# PCB-REMCON.net
KiCad netlist of a schematic drawn in EAGLE
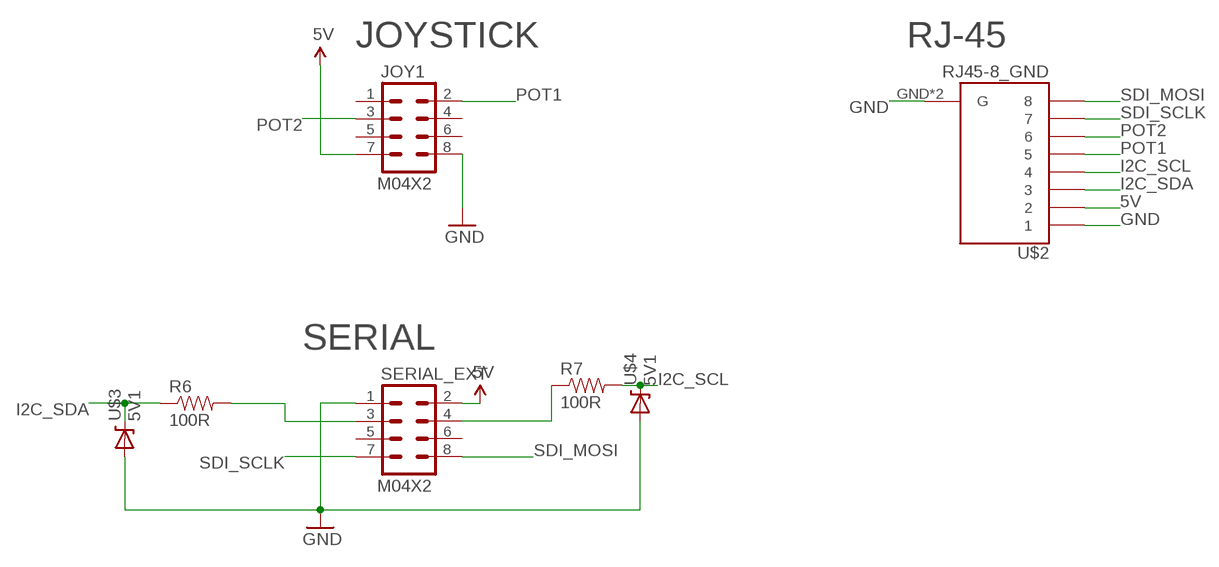
[diagram p0: schematic, sheet 1]

(export (version "E")
  (design (tool "Eeschema 10.0.6"))
  (components
    (comp (ref "JOY1")
      (value "M04X2")
      (footprint "eagle-import:2X4")
      (libsource (lib "eagle-import") (part "M04X2"))
    )
    (comp (ref "R6")
      (value "100R")
      (footprint "eagle-import:0603-RES")
      (libsource (lib "eagle-import") (part "RESISTOR0603-RES"))
    )
    (comp (ref "R7")
      (value "100R")
      (footprint "eagle-import:0603-RES")
      (libsource (lib "eagle-import") (part "RESISTOR0603-RES"))
    )
    (comp (ref "SERIAL_EXT")
      (value "M04X2")
      (footprint "eagle-import:2X4")
      (libsource (lib "eagle-import") (part "M04X2"))
    )
    (comp (ref "U$2")
      (value "RJ45-8_GND")
      (footprint "eagle-import:RJ45-8_GND")
      (libsource (lib "eagle-import") (part "RJ45-8_GND"))
    )
    (comp (ref "U$3")
      (value "5V1")
      (footprint "eagle-import:DIODE-ZENER")
      (libsource (lib "eagle-import") (part "DIODE-ZENERPTH"))
    )
    (comp (ref "U$4")
      (value "5V1")
      (footprint "eagle-import:DIODE-ZENER")
      (libsource (lib "eagle-import") (part "DIODE-ZENERPTH"))
    )
  )
  (nets
    (net (code "1") (name "/I2C_SCL") (class "Default")
      (node (ref "R7") (pin "2") (pinfunction "2_2") (pintype "passive"))
      (node (ref "U$2") (pin "4") (pinfunction "4_4") (pintype "bidirectional"))
      (node (ref "U$4") (pin "P$1") (pinfunction "C_P$1") (pintype "passive"))
    )
    (net (code "2") (name "/I2C_SDA") (class "Default")
      (node (ref "R6") (pin "1") (pinfunction "1_1") (pintype "passive"))
      (node (ref "U$2") (pin "3") (pinfunction "3_3") (pintype "bidirectional"))
      (node (ref "U$3") (pin "P$1") (pinfunction "C_P$1") (pintype "passive"))
    )
    (net (code "3") (name "/POT1") (class "Default")
      (node (ref "JOY1") (pin "2") (pinfunction "2_2") (pintype "passive"))
      (node (ref "U$2") (pin "5") (pinfunction "5_5") (pintype "bidirectional"))
    )
    (net (code "4") (name "/POT2") (class "Default")
      (node (ref "JOY1") (pin "3") (pinfunction "3_3") (pintype "passive"))
      (node (ref "U$2") (pin "6") (pinfunction "6_6") (pintype "bidirectional"))
    )
    (net (code "5") (name "/SDI_MOSI") (class "Default")
      (node (ref "SERIAL_EXT") (pin "8") (pinfunction "8_8") (pintype "passive"))
      (node (ref "U$2") (pin "8") (pinfunction "8_8") (pintype "bidirectional"))
    )
    (net (code "6") (name "/SDI_SCLK") (class "Default")
      (node (ref "SERIAL_EXT") (pin "7") (pinfunction "7_7") (pintype "passive"))
      (node (ref "U$2") (pin "7") (pinfunction "7_7") (pintype "bidirectional"))
    )
    (net (code "7") (name "5V") (class "Default")
      (node (ref "JOY1") (pin "7") (pinfunction "7_7") (pintype "passive"))
      (node (ref "SERIAL_EXT") (pin "2") (pinfunction "2_2") (pintype "passive"))
      (node (ref "U$2") (pin "2") (pinfunction "2_2") (pintype "bidirectional"))
    )
    (net (code "8") (name "GND") (class "Default")
      (node (ref "JOY1") (pin "8") (pinfunction "8_8") (pintype "passive"))
      (node (ref "SERIAL_EXT") (pin "1") (pinfunction "1_1") (pintype "passive"))
      (node (ref "U$2") (pin "1") (pinfunction "1_1") (pintype "bidirectional"))
      (node (ref "U$2") (pin "GND") (pinfunction "G_GND") (pintype "power_in"))
      (node (ref "U$2") (pin "GND1") (pinfunction "G_GND1") (pintype "power_in"))
      (node (ref "U$3") (pin "P$2") (pinfunction "A_P$2") (pintype "passive"))
      (node (ref "U$4") (pin "P$2") (pinfunction "A_P$2") (pintype "passive"))
    )
    (net (code "9") (name "Net-(R6-Pad2)") (class "Default")
      (node (ref "R6") (pin "2") (pinfunction "2_2") (pintype "passive"))
      (node (ref "SERIAL_EXT") (pin "3") (pinfunction "3_3") (pintype "passive"))
    )
    (net (code "10") (name "Net-(R7-Pad1)") (class "Default")
      (node (ref "R7") (pin "1") (pinfunction "1_1") (pintype "passive"))
      (node (ref "SERIAL_EXT") (pin "4") (pinfunction "4_4") (pintype "passive"))
    )
    (net (code "11") (name "unconnected-(JOY1-Pad1)") (class "Default")
      (node (ref "JOY1") (pin "1") (pinfunction "1_1") (pintype "passive"))
    )
    (net (code "12") (name "unconnected-(JOY1-Pad4)") (class "Default")
      (node (ref "JOY1") (pin "4") (pinfunction "4_4") (pintype "passive"))
    )
    (net (code "13") (name "unconnected-(JOY1-Pad5)") (class "Default")
      (node (ref "JOY1") (pin "5") (pinfunction "5_5") (pintype "passive"))
    )
    (net (code "14") (name "unconnected-(JOY1-Pad6)") (class "Default")
      (node (ref "JOY1") (pin "6") (pinfunction "6_6") (pintype "passive"))
    )
    (net (code "15") (name "unconnected-(SERIAL_EXT-Pad5)") (class "Default")
      (node (ref "SERIAL_EXT") (pin "5") (pinfunction "5_5") (pintype "passive"))
    )
    (net (code "16") (name "unconnected-(SERIAL_EXT-Pad6)") (class "Default")
      (node (ref "SERIAL_EXT") (pin "6") (pinfunction "6_6") (pintype "passive"))
    )
  )
)
